# pi433_r00.net
KiCad netlist of a schematic drawn in EAGLE
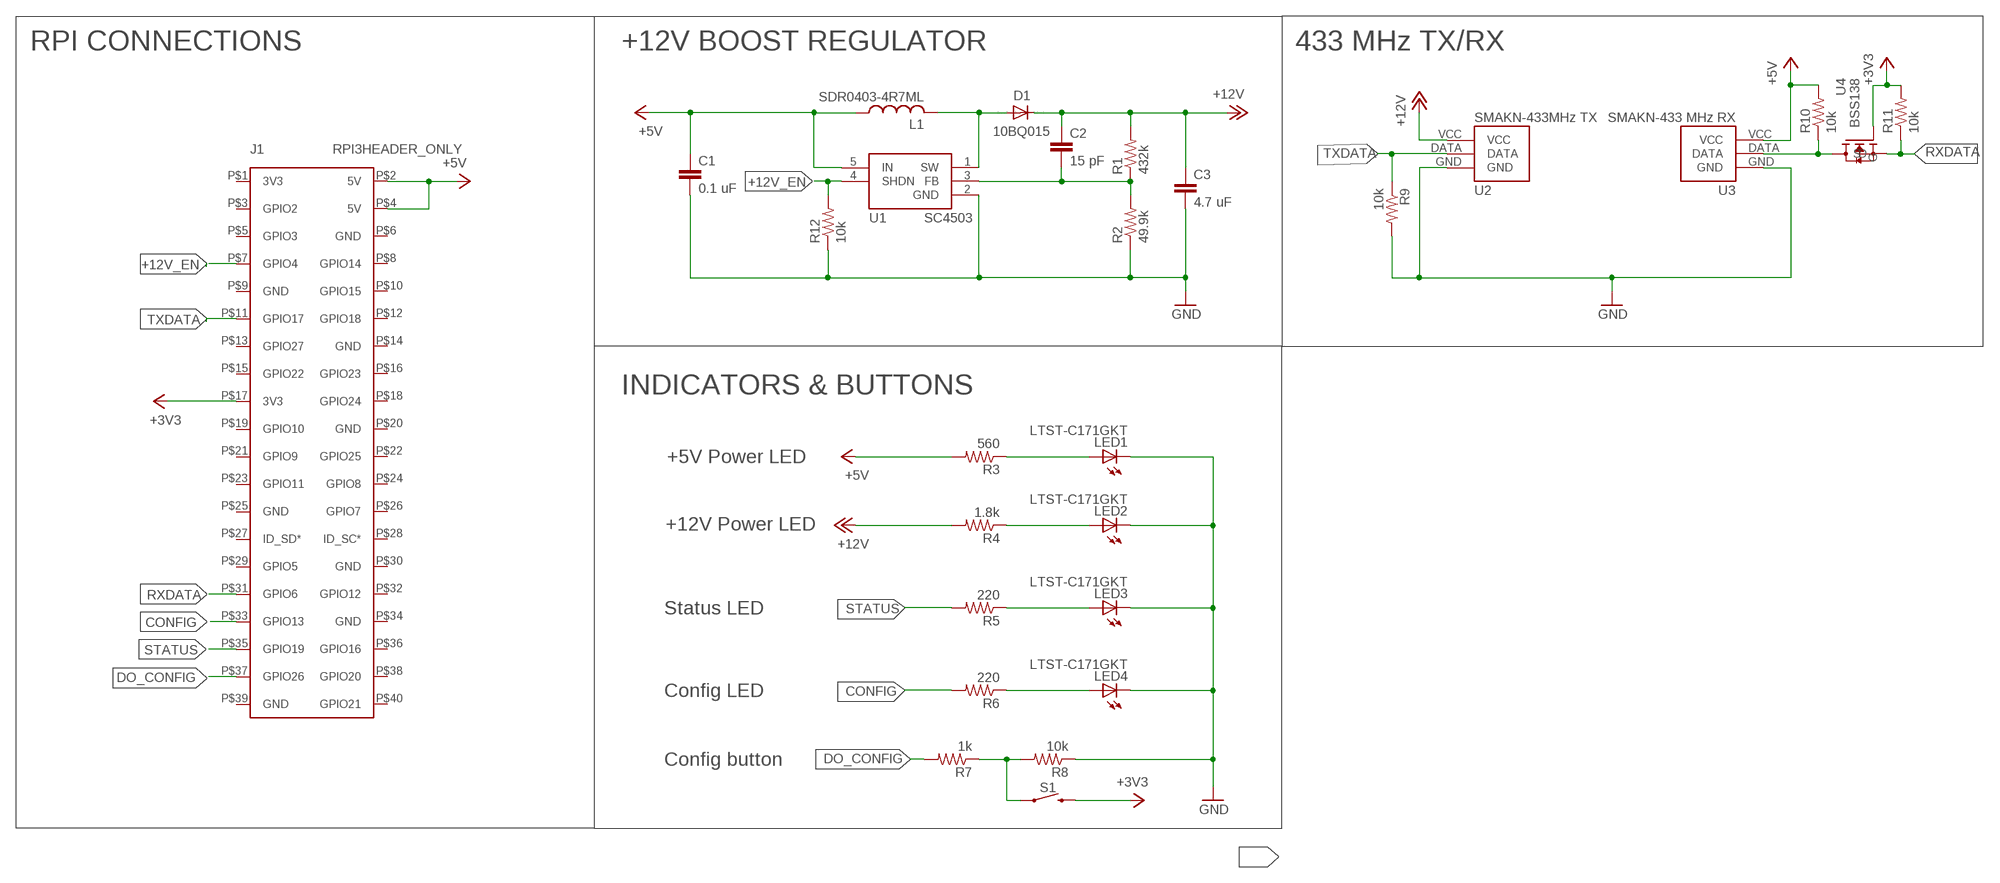
[diagram p0: schematic, sheet 1]

(export (version "E")
  (design (tool "Eeschema 10.0.6"))
  (components
    (comp (ref "C1")
      (value "0.1 uF")
      (footprint "eagle-import:C0603")
      (libsource (lib "eagle-import") (part "C-EUC0603"))
    )
    (comp (ref "C2")
      (value "15 pF")
      (footprint "eagle-import:C0603")
      (libsource (lib "eagle-import") (part "C-EUC0603"))
    )
    (comp (ref "C3")
      (value "4.7 uF")
      (footprint "eagle-import:C0805")
      (libsource (lib "eagle-import") (part "C-EUC0805"))
    )
    (comp (ref "D1")
      (value "10BQ015")
      (footprint "eagle-import:DO214AA")
      (libsource (lib "eagle-import") (part "DIODE-DO214AA"))
    )
    (comp (ref "J1")
      (value "RPI3HEADER_ONLY")
      (footprint "eagle-import:RPI3-HEADER_ONLY")
      (libsource (lib "eagle-import") (part "RPI3HEADER_ONLY"))
    )
    (comp (ref "L1")
      (value "SDR0403-4R7ML")
      (footprint "eagle-import:SDR0403")
      (libsource (lib "eagle-import") (part "SDR0403-4R7ML"))
    )
    (comp (ref "LED1")
      (value "LTST-C171GKT")
      (footprint "eagle-import:CHIPLED_0805")
      (libsource (lib "eagle-import") (part "LEDCHIPLED_0805"))
    )
    (comp (ref "LED2")
      (value "LTST-C171GKT")
      (footprint "eagle-import:CHIPLED_0805")
      (libsource (lib "eagle-import") (part "LEDCHIPLED_0805"))
    )
    (comp (ref "LED3")
      (value "LTST-C171GKT")
      (footprint "eagle-import:CHIPLED_0805")
      (libsource (lib "eagle-import") (part "LEDCHIPLED_0805"))
    )
    (comp (ref "LED4")
      (value "LTST-C171GKT")
      (footprint "eagle-import:CHIPLED_0805")
      (libsource (lib "eagle-import") (part "LEDCHIPLED_0805"))
    )
    (comp (ref "R1")
      (value "432k")
      (footprint "eagle-import:R0805")
      (libsource (lib "eagle-import") (part "R-US_R0805"))
    )
    (comp (ref "R2")
      (value "49.9k")
      (footprint "eagle-import:R0805")
      (libsource (lib "eagle-import") (part "R-US_R0805"))
    )
    (comp (ref "R3")
      (value "560")
      (footprint "eagle-import:R0805")
      (libsource (lib "eagle-import") (part "R-US_R0805"))
    )
    (comp (ref "R4")
      (value "1.8k")
      (footprint "eagle-import:R0805")
      (libsource (lib "eagle-import") (part "R-US_R0805"))
    )
    (comp (ref "R5")
      (value "220")
      (footprint "eagle-import:R0805")
      (libsource (lib "eagle-import") (part "R-US_R0805"))
    )
    (comp (ref "R6")
      (value "220")
      (footprint "eagle-import:R0805")
      (libsource (lib "eagle-import") (part "R-US_R0805"))
    )
    (comp (ref "R7")
      (value "1k")
      (footprint "eagle-import:R0805")
      (libsource (lib "eagle-import") (part "R-US_R0805"))
    )
    (comp (ref "R8")
      (value "10k")
      (footprint "eagle-import:R0805")
      (libsource (lib "eagle-import") (part "R-US_R0805"))
    )
    (comp (ref "R9")
      (value "10k")
      (footprint "eagle-import:R0805")
      (libsource (lib "eagle-import") (part "R-US_R0805"))
    )
    (comp (ref "R10")
      (value "10k")
      (footprint "eagle-import:R0805")
      (libsource (lib "eagle-import") (part "R-US_R0805"))
    )
    (comp (ref "R11")
      (value "10k")
      (footprint "eagle-import:R0805")
      (libsource (lib "eagle-import") (part "R-US_R0805"))
    )
    (comp (ref "R12")
      (value "10k")
      (footprint "eagle-import:R0805")
      (libsource (lib "eagle-import") (part "R-US_R0805"))
    )
    (comp (ref "S1")
      (value "MOMENTARY-SWITCH-SPST-SMD-6.0X3.5MM")
      (footprint "eagle-import:TACTILE_SWITCH_SMD_6.0X3.5MM")
      (libsource (lib "eagle-import") (part "MOMENTARY-SWITCH-SPST-SMD-6.0X3.5MM"))
    )
    (comp (ref "U1")
      (value "SC4503")
      (footprint "eagle-import:TSOT-23-5")
      (libsource (lib "eagle-import") (part "SC4503"))
    )
    (comp (ref "U2")
      (value "SMAKN-433TX")
      (footprint "eagle-import:SMAKN-433TX")
      (libsource (lib "eagle-import") (part "SMAKN-433TX"))
    )
    (comp (ref "U3")
      (value "SMAKN-433RX")
      (footprint "eagle-import:SMAKN-433RX")
      (libsource (lib "eagle-import") (part "SMAKN-433RX"))
    )
    (comp (ref "U4")
      (value "BSS138")
      (footprint "eagle-import:BSS138")
      (fields (field (name "MF") "Fairchild Semiconductor"))
      (libsource (lib "eagle-import") (part "BSS138"))
    )
  )
  (nets
    (net (code "1") (name "+3V3") (class "Default")
      (node (ref "J1") (pin "P$17") (pinfunction "3V3_P$17") (pintype "bidirectional"))
      (node (ref "R11") (pin "2") (pinfunction "2_2") (pintype "passive"))
      (node (ref "S1") (pin "2") (pinfunction "2_2") (pintype "passive"))
      (node (ref "U4") (pin "G") (pinfunction "G_G") (pintype "passive"))
    )
    (net (code "2") (name "+5V") (class "Default")
      (node (ref "C1") (pin "1") (pinfunction "1_1") (pintype "passive"))
      (node (ref "J1") (pin "P$2") (pinfunction "5V_P$2") (pintype "bidirectional"))
      (node (ref "J1") (pin "P$4") (pinfunction "5V_P$4") (pintype "bidirectional"))
      (node (ref "L1") (pin "P$1") (pinfunction "1_P$1") (pintype "passive"))
      (node (ref "R10") (pin "2") (pinfunction "2_2") (pintype "passive"))
      (node (ref "R3") (pin "2") (pinfunction "2_2") (pintype "passive"))
      (node (ref "U1") (pin "5") (pinfunction "IN_5") (pintype "power_in"))
      (node (ref "U3") (pin "VCC") (pinfunction "VCC_VCC") (pintype "bidirectional"))
    )
    (net (code "3") (name "+12V") (class "Default")
      (node (ref "C2") (pin "1") (pinfunction "1_1") (pintype "passive"))
      (node (ref "C3") (pin "1") (pinfunction "1_1") (pintype "passive"))
      (node (ref "D1") (pin "C") (pinfunction "C_C") (pintype "passive"))
      (node (ref "R1") (pin "2") (pinfunction "2_2") (pintype "passive"))
      (node (ref "R4") (pin "2") (pinfunction "2_2") (pintype "passive"))
      (node (ref "U2") (pin "VCC") (pinfunction "VCC_VCC") (pintype "bidirectional"))
    )
    (net (code "4") (name "/+12V_EN") (class "Default")
      (node (ref "J1") (pin "P$7") (pinfunction "GPIO4_P$7") (pintype "bidirectional"))
      (node (ref "R12") (pin "2") (pinfunction "2_2") (pintype "passive"))
      (node (ref "U1") (pin "4") (pinfunction "SHDN_4") (pintype "input"))
    )
    (net (code "5") (name "/CONFIG") (class "Default")
      (node (ref "J1") (pin "P$33") (pinfunction "GPIO13_P$33") (pintype "bidirectional"))
      (node (ref "R6") (pin "2") (pinfunction "2_2") (pintype "passive"))
    )
    (net (code "6") (name "/DO_CONFIG") (class "Default")
      (node (ref "J1") (pin "P$37") (pinfunction "GPIO26_P$37") (pintype "bidirectional"))
      (node (ref "R7") (pin "2") (pinfunction "2_2") (pintype "passive"))
    )
    (net (code "7") (name "/RXDATA") (class "Default")
      (node (ref "J1") (pin "P$31") (pinfunction "GPIO6_P$31") (pintype "bidirectional"))
      (node (ref "R11") (pin "1") (pinfunction "1_1") (pintype "passive"))
      (node (ref "U4") (pin "S") (pinfunction "S_S") (pintype "passive"))
    )
    (net (code "8") (name "/STATUS") (class "Default")
      (node (ref "J1") (pin "P$35") (pinfunction "GPIO19_P$35") (pintype "bidirectional"))
      (node (ref "R5") (pin "2") (pinfunction "2_2") (pintype "passive"))
    )
    (net (code "9") (name "/TXDATA") (class "Default")
      (node (ref "J1") (pin "P$11") (pinfunction "GPIO17_P$11") (pintype "bidirectional"))
      (node (ref "R9") (pin "1") (pinfunction "1_1") (pintype "passive"))
      (node (ref "U2") (pin "DATA") (pinfunction "DATA_DATA") (pintype "bidirectional"))
    )
    (net (code "10") (name "GND") (class "Default")
      (node (ref "C1") (pin "2") (pinfunction "2_2") (pintype "passive"))
      (node (ref "C3") (pin "2") (pinfunction "2_2") (pintype "passive"))
      (node (ref "LED1") (pin "C") (pinfunction "C_C") (pintype "passive"))
      (node (ref "LED2") (pin "C") (pinfunction "C_C") (pintype "passive"))
      (node (ref "LED3") (pin "C") (pinfunction "C_C") (pintype "passive"))
      (node (ref "LED4") (pin "C") (pinfunction "C_C") (pintype "passive"))
      (node (ref "R12") (pin "1") (pinfunction "1_1") (pintype "passive"))
      (node (ref "R2") (pin "1") (pinfunction "1_1") (pintype "passive"))
      (node (ref "R8") (pin "1") (pinfunction "1_1") (pintype "passive"))
      (node (ref "R9") (pin "2") (pinfunction "2_2") (pintype "passive"))
      (node (ref "U1") (pin "2") (pinfunction "GND_2") (pintype "input"))
      (node (ref "U2") (pin "GND") (pinfunction "GND_GND") (pintype "bidirectional"))
      (node (ref "U3") (pin "GND") (pinfunction "GND_GND") (pintype "bidirectional"))
    )
    (net (code "11") (name "Net-(L1-2)") (class "Default")
      (node (ref "D1") (pin "A") (pinfunction "A_A") (pintype "passive"))
      (node (ref "L1") (pin "P$2") (pinfunction "2_P$2") (pintype "passive"))
      (node (ref "U1") (pin "1") (pinfunction "SW_1") (pintype "input"))
    )
    (net (code "12") (name "Net-(LED1-PadA)") (class "Default")
      (node (ref "LED1") (pin "A") (pinfunction "A_A") (pintype "passive"))
      (node (ref "R3") (pin "1") (pinfunction "1_1") (pintype "passive"))
    )
    (net (code "13") (name "Net-(LED2-PadA)") (class "Default")
      (node (ref "LED2") (pin "A") (pinfunction "A_A") (pintype "passive"))
      (node (ref "R4") (pin "1") (pinfunction "1_1") (pintype "passive"))
    )
    (net (code "14") (name "Net-(LED3-PadA)") (class "Default")
      (node (ref "LED3") (pin "A") (pinfunction "A_A") (pintype "passive"))
      (node (ref "R5") (pin "1") (pinfunction "1_1") (pintype "passive"))
    )
    (net (code "15") (name "Net-(LED4-PadA)") (class "Default")
      (node (ref "LED4") (pin "A") (pinfunction "A_A") (pintype "passive"))
      (node (ref "R6") (pin "1") (pinfunction "1_1") (pintype "passive"))
    )
    (net (code "16") (name "Net-(R7-Pad1)") (class "Default")
      (node (ref "R7") (pin "1") (pinfunction "1_1") (pintype "passive"))
      (node (ref "R8") (pin "2") (pinfunction "2_2") (pintype "passive"))
      (node (ref "S1") (pin "1") (pinfunction "1_1") (pintype "passive"))
    )
    (net (code "17") (name "Net-(R10-Pad1)") (class "Default")
      (node (ref "R10") (pin "1") (pinfunction "1_1") (pintype "passive"))
      (node (ref "U3") (pin "DATA") (pinfunction "DATA_DATA") (pintype "bidirectional"))
      (node (ref "U4") (pin "D") (pinfunction "D_D") (pintype "passive"))
    )
    (net (code "18") (name "Net-(U1-FB)") (class "Default")
      (node (ref "C2") (pin "2") (pinfunction "2_2") (pintype "passive"))
      (node (ref "R1") (pin "1") (pinfunction "1_1") (pintype "passive"))
      (node (ref "R2") (pin "2") (pinfunction "2_2") (pintype "passive"))
      (node (ref "U1") (pin "3") (pinfunction "FB_3") (pintype "input"))
    )
    (net (code "19") (name "unconnected-(J1-3V3-PadP$1)") (class "Default")
      (node (ref "J1") (pin "P$1") (pinfunction "3V3_P$1") (pintype "bidirectional"))
    )
    (net (code "20") (name "unconnected-(J1-GND-PadP$6)") (class "Default")
      (node (ref "J1") (pin "P$6") (pinfunction "GND_P$6") (pintype "bidirectional"))
    )
    (net (code "21") (name "unconnected-(J1-GND-PadP$9)") (class "Default")
      (node (ref "J1") (pin "P$9") (pinfunction "GND_P$9") (pintype "bidirectional"))
    )
    (net (code "22") (name "unconnected-(J1-GND-PadP$14)") (class "Default")
      (node (ref "J1") (pin "P$14") (pinfunction "GND_P$14") (pintype "bidirectional"))
    )
    (net (code "23") (name "unconnected-(J1-GND-PadP$20)") (class "Default")
      (node (ref "J1") (pin "P$20") (pinfunction "GND_P$20") (pintype "bidirectional"))
    )
    (net (code "24") (name "unconnected-(J1-GND-PadP$25)") (class "Default")
      (node (ref "J1") (pin "P$25") (pinfunction "GND_P$25") (pintype "bidirectional"))
    )
    (net (code "25") (name "unconnected-(J1-GND-PadP$30)") (class "Default")
      (node (ref "J1") (pin "P$30") (pinfunction "GND_P$30") (pintype "bidirectional"))
    )
    (net (code "26") (name "unconnected-(J1-GND-PadP$34)") (class "Default")
      (node (ref "J1") (pin "P$34") (pinfunction "GND_P$34") (pintype "bidirectional"))
    )
    (net (code "27") (name "unconnected-(J1-GND-PadP$39)") (class "Default")
      (node (ref "J1") (pin "P$39") (pinfunction "GND_P$39") (pintype "bidirectional"))
    )
    (net (code "28") (name "unconnected-(J1-GPIO2-PadP$3)") (class "Default")
      (node (ref "J1") (pin "P$3") (pinfunction "GPIO2_P$3") (pintype "bidirectional"))
    )
    (net (code "29") (name "unconnected-(J1-GPIO3-PadP$5)") (class "Default")
      (node (ref "J1") (pin "P$5") (pinfunction "GPIO3_P$5") (pintype "bidirectional"))
    )
    (net (code "30") (name "unconnected-(J1-GPIO5-PadP$29)") (class "Default")
      (node (ref "J1") (pin "P$29") (pinfunction "GPIO5_P$29") (pintype "bidirectional"))
    )
    (net (code "31") (name "unconnected-(J1-GPIO7-PadP$26)") (class "Default")
      (node (ref "J1") (pin "P$26") (pinfunction "GPIO7_P$26") (pintype "bidirectional"))
    )
    (net (code "32") (name "unconnected-(J1-GPIO8-PadP$24)") (class "Default")
      (node (ref "J1") (pin "P$24") (pinfunction "GPIO8_P$24") (pintype "bidirectional"))
    )
    (net (code "33") (name "unconnected-(J1-GPIO9-PadP$21)") (class "Default")
      (node (ref "J1") (pin "P$21") (pinfunction "GPIO9_P$21") (pintype "bidirectional"))
    )
    (net (code "34") (name "unconnected-(J1-GPIO10-PadP$19)") (class "Default")
      (node (ref "J1") (pin "P$19") (pinfunction "GPIO10_P$19") (pintype "bidirectional"))
    )
    (net (code "35") (name "unconnected-(J1-GPIO11-PadP$23)") (class "Default")
      (node (ref "J1") (pin "P$23") (pinfunction "GPIO11_P$23") (pintype "bidirectional"))
    )
    (net (code "36") (name "unconnected-(J1-GPIO12-PadP$32)") (class "Default")
      (node (ref "J1") (pin "P$32") (pinfunction "GPIO12_P$32") (pintype "bidirectional"))
    )
    (net (code "37") (name "unconnected-(J1-GPIO14-PadP$8)") (class "Default")
      (node (ref "J1") (pin "P$8") (pinfunction "GPIO14_P$8") (pintype "bidirectional"))
    )
    (net (code "38") (name "unconnected-(J1-GPIO15-PadP$10)") (class "Default")
      (node (ref "J1") (pin "P$10") (pinfunction "GPIO15_P$10") (pintype "bidirectional"))
    )
    (net (code "39") (name "unconnected-(J1-GPIO16-PadP$36)") (class "Default")
      (node (ref "J1") (pin "P$36") (pinfunction "GPIO16_P$36") (pintype "bidirectional"))
    )
    (net (code "40") (name "unconnected-(J1-GPIO18-PadP$12)") (class "Default")
      (node (ref "J1") (pin "P$12") (pinfunction "GPIO18_P$12") (pintype "bidirectional"))
    )
    (net (code "41") (name "unconnected-(J1-GPIO20-PadP$38)") (class "Default")
      (node (ref "J1") (pin "P$38") (pinfunction "GPIO20_P$38") (pintype "bidirectional"))
    )
    (net (code "42") (name "unconnected-(J1-GPIO21-PadP$40)") (class "Default")
      (node (ref "J1") (pin "P$40") (pinfunction "GPIO21_P$40") (pintype "bidirectional"))
    )
    (net (code "43") (name "unconnected-(J1-GPIO22-PadP$15)") (class "Default")
      (node (ref "J1") (pin "P$15") (pinfunction "GPIO22_P$15") (pintype "bidirectional"))
    )
    (net (code "44") (name "unconnected-(J1-GPIO23-PadP$16)") (class "Default")
      (node (ref "J1") (pin "P$16") (pinfunction "GPIO23_P$16") (pintype "bidirectional"))
    )
    (net (code "45") (name "unconnected-(J1-GPIO24-PadP$18)") (class "Default")
      (node (ref "J1") (pin "P$18") (pinfunction "GPIO24_P$18") (pintype "bidirectional"))
    )
    (net (code "46") (name "unconnected-(J1-GPIO25-PadP$22)") (class "Default")
      (node (ref "J1") (pin "P$22") (pinfunction "GPIO25_P$22") (pintype "bidirectional"))
    )
    (net (code "47") (name "unconnected-(J1-GPIO27-PadP$13)") (class "Default")
      (node (ref "J1") (pin "P$13") (pinfunction "GPIO27_P$13") (pintype "bidirectional"))
    )
    (net (code "48") (name "unconnected-(J1-ID_SC*-PadP$28)") (class "Default")
      (node (ref "J1") (pin "P$28") (pinfunction "ID_SC*_P$28") (pintype "bidirectional"))
    )
    (net (code "49") (name "unconnected-(J1-ID_SD*-PadP$27)") (class "Default")
      (node (ref "J1") (pin "P$27") (pinfunction "ID_SD*_P$27") (pintype "bidirectional"))
    )
  )
)
